# SmartThermo2_0.net
KiCad netlist of a schematic drawn in EAGLE
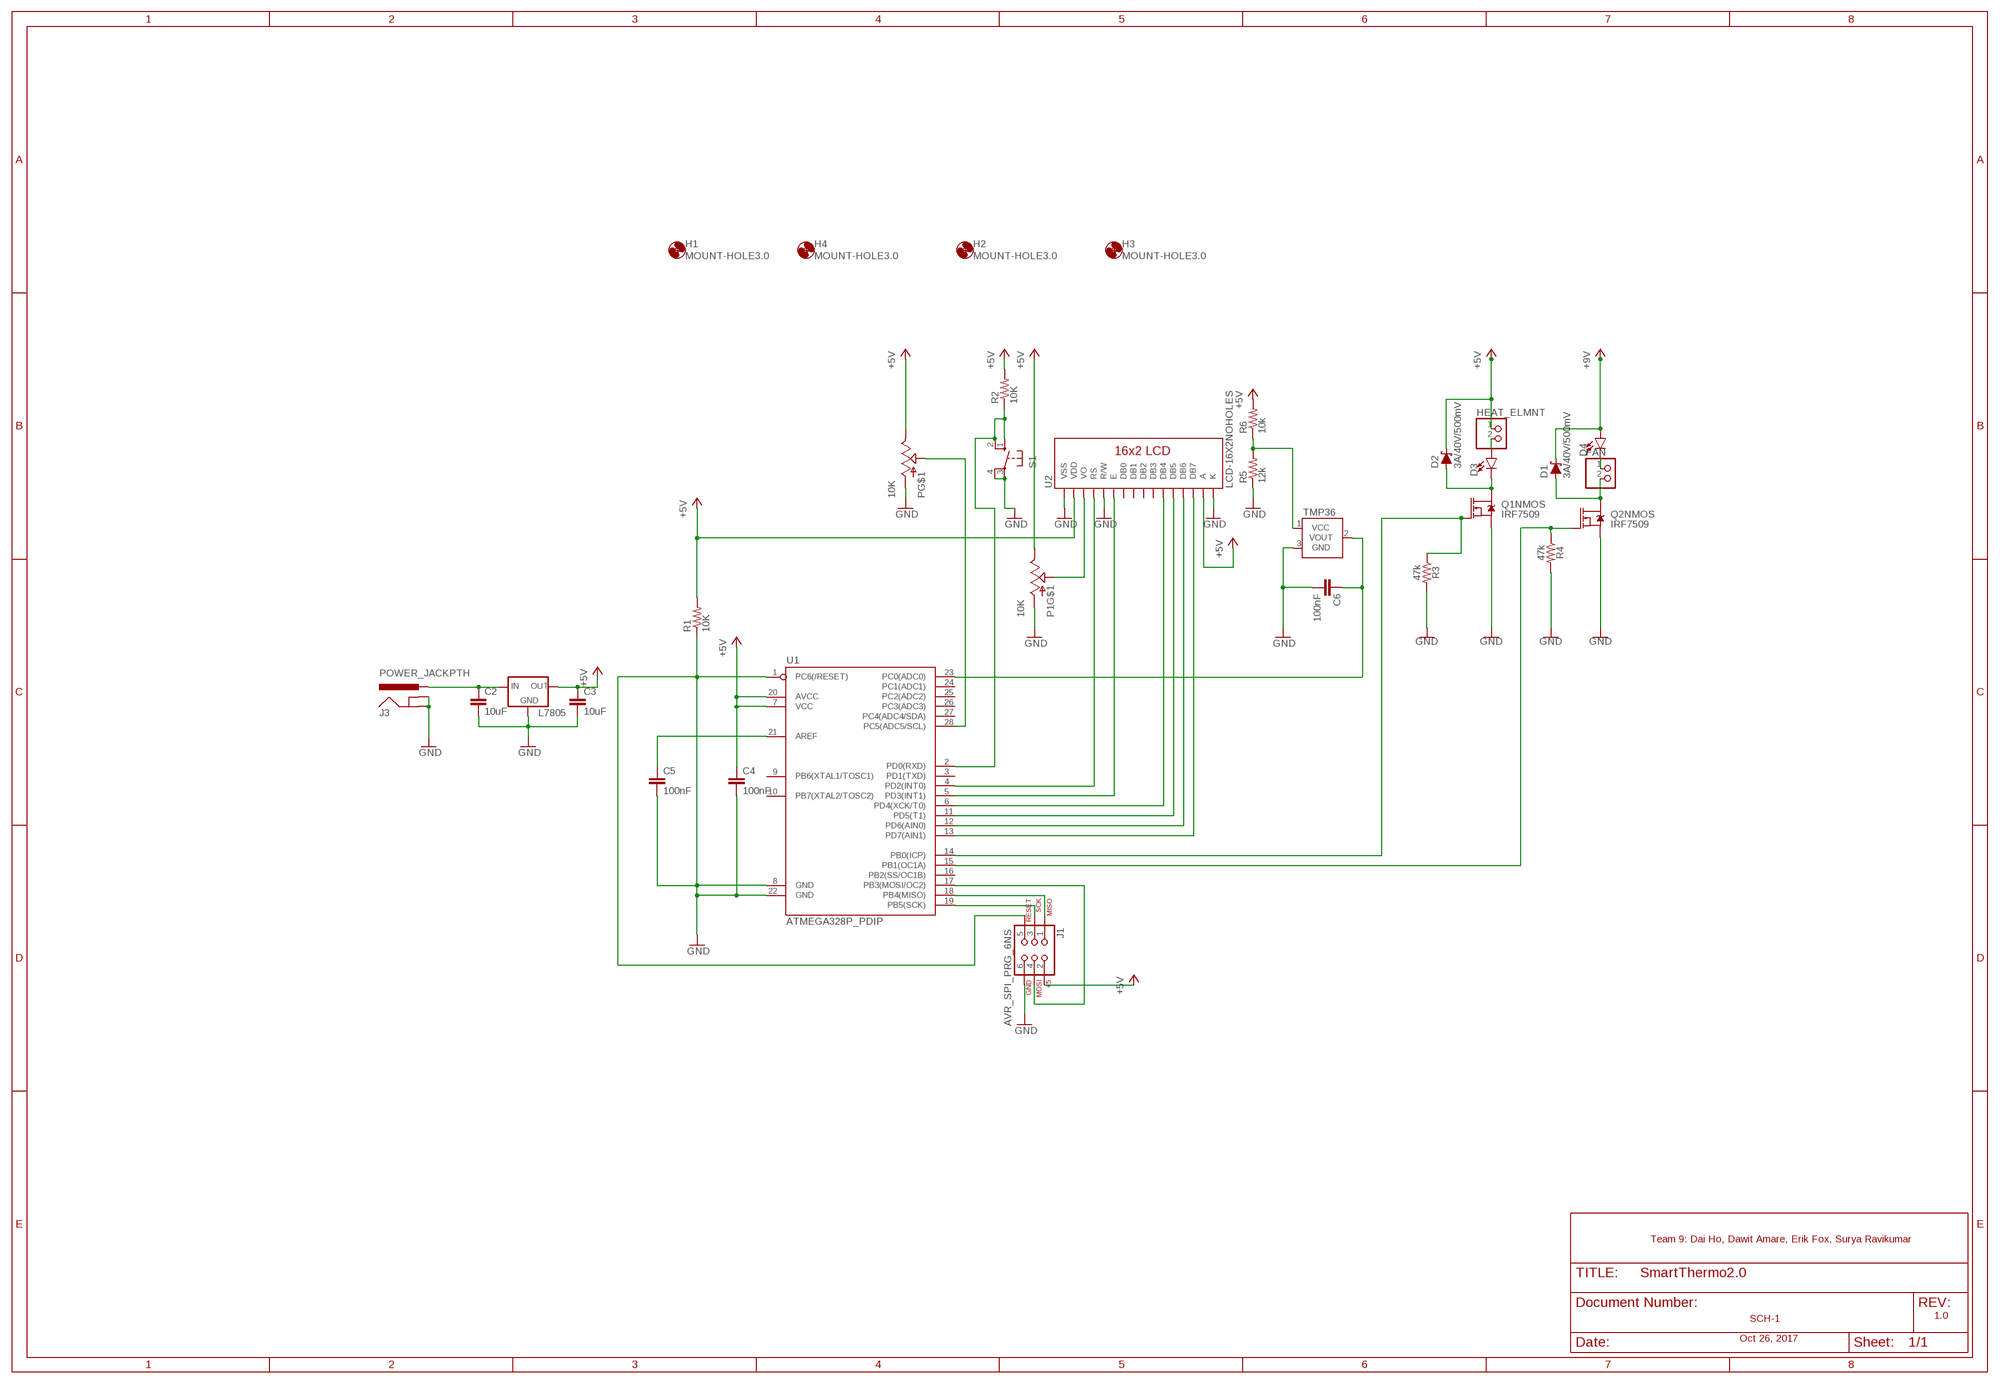
[diagram p0: schematic, sheet 1]

(export (version "E")
  (design (tool "Eeschema 10.0.6"))
  (components
    (comp (ref "C2")
      (value "10uF")
      (footprint "eagle-import:C7.5B3")
      (libsource (lib "eagle-import") (part "C7.5/3"))
    )
    (comp (ref "C3")
      (value "10uF")
      (footprint "eagle-import:C7.5B3")
      (libsource (lib "eagle-import") (part "C7.5/3"))
    )
    (comp (ref "C4")
      (value "100nF")
      (footprint "eagle-import:C2.5-2")
      (libsource (lib "eagle-import") (part "C2.5/2"))
    )
    (comp (ref "C5")
      (value "100nF")
      (footprint "eagle-import:C2.5-2")
      (libsource (lib "eagle-import") (part "C2.5/2"))
    )
    (comp (ref "C6")
      (value "100nF")
      (footprint "eagle-import:C2.5-2")
      (libsource (lib "eagle-import") (part "C2.5/2"))
    )
    (comp (ref "D1")
      (value "3A/40V/500mV")
      (footprint "eagle-import:SMA-DIODE")
      (libsource (lib "eagle-import") (part "DIODE-SCHOTTKY-B340A"))
    )
    (comp (ref "D2")
      (value "3A/40V/500mV")
      (footprint "eagle-import:SMA-DIODE")
      (libsource (lib "eagle-import") (part "DIODE-SCHOTTKY-B340A"))
    )
    (comp (ref "D3")
      (value "LED3MM")
      (footprint "eagle-import:LED_3MM")
      (libsource (lib "eagle-import") (part "LED3MM"))
    )
    (comp (ref "D4")
      (value "LED3MM")
      (footprint "eagle-import:LED_3MM")
      (libsource (lib "eagle-import") (part "LED3MM"))
    )
    (comp (ref "FAN")
      (value "PINHD-1X2/90")
      (footprint "eagle-import:1X02_90")
      (libsource (lib "eagle-import") (part "PINHD-1X2/90"))
    )
    (comp (ref "H1")
      (value "MOUNT-HOLE3.0")
      (footprint "eagle-import:3,0")
      (libsource (lib "eagle-import") (part "MOUNT-HOLE3.0"))
    )
    (comp (ref "H2")
      (value "MOUNT-HOLE3.0")
      (footprint "eagle-import:3,0")
      (libsource (lib "eagle-import") (part "MOUNT-HOLE3.0"))
    )
    (comp (ref "H3")
      (value "MOUNT-HOLE3.0")
      (footprint "eagle-import:3,0")
      (libsource (lib "eagle-import") (part "MOUNT-HOLE3.0"))
    )
    (comp (ref "H4")
      (value "MOUNT-HOLE3.0")
      (footprint "eagle-import:3,0")
      (libsource (lib "eagle-import") (part "MOUNT-HOLE3.0"))
    )
    (comp (ref "HEAT_ELMNT")
      (value "PINHD-1X2/90")
      (footprint "eagle-import:1X02_90")
      (libsource (lib "eagle-import") (part "PINHD-1X2/90"))
    )
    (comp (ref "J1")
      (value "AVR_SPI_PRG_6NS")
      (footprint "eagle-import:2X3-NS")
      (libsource (lib "eagle-import") (part "AVR_SPI_PRG_6NS"))
    )
    (comp (ref "J3")
      (value "POWER_JACKPTH")
      (footprint "eagle-import:POWER_JACK_PTH")
      (libsource (lib "eagle-import") (part "POWER_JACKPTH"))
    )
    (comp (ref "L7805")
      (value "78XXL")
      (footprint "eagle-import:78XXL")
      (libsource (lib "eagle-import") (part "78XXL"))
    )
    (comp (ref "P")
      (value "10K")
      (footprint "eagle-import:POT_PTH")
      (libsource (lib "eagle-import") (part "POT_SWITCHPOT_PTH"))
    )
    (comp (ref "P1")
      (value "10K")
      (footprint "eagle-import:POT_PTH")
      (libsource (lib "eagle-import") (part "POT_SWITCHPOT_PTH"))
    )
    (comp (ref "Q1")
      (value "IRF7509")
      (footprint "eagle-import:MSOP8")
      (libsource (lib "eagle-import") (part "IRF7509"))
    )
    (comp (ref "Q2")
      (value "IRF7509")
      (footprint "eagle-import:MSOP8")
      (libsource (lib "eagle-import") (part "IRF7509"))
    )
    (comp (ref "R1")
      (value "10K")
      (footprint "eagle-import:1206")
      (libsource (lib "eagle-import") (part "RESISTOR1206"))
    )
    (comp (ref "R2")
      (value "10K")
      (footprint "eagle-import:1206")
      (libsource (lib "eagle-import") (part "RESISTOR1206"))
    )
    (comp (ref "R3")
      (value "47k")
      (footprint "eagle-import:0603")
      (libsource (lib "eagle-import") (part "47KOHM-0603-1/10W-1%"))
    )
    (comp (ref "R4")
      (value "47k")
      (footprint "eagle-import:0603")
      (libsource (lib "eagle-import") (part "47KOHM-0603-1/10W-1%"))
    )
    (comp (ref "R5")
      (value "12k")
      (footprint "eagle-import:0204_5")
      (libsource (lib "eagle-import") (part "R-US_0204/5"))
    )
    (comp (ref "R6")
      (value "10k")
      (footprint "eagle-import:0204_5")
      (libsource (lib "eagle-import") (part "R-US_0204/5"))
    )
    (comp (ref "S1")
      (value "10-XX")
      (footprint "eagle-import:B3F-10XX")
      (fields (field (name "MPN") "B3F-1000"))
      (libsource (lib "eagle-import") (part "10-XX"))
    )
    (comp (ref "TMP36")
      (value "TMP36GT9")
      (footprint "eagle-import:TO-92")
      (libsource (lib "eagle-import") (part "TMP36GT9"))
    )
    (comp (ref "U1")
      (value "ATMEGA328P_PDIP")
      (footprint "eagle-import:DIL28-3")
      (libsource (lib "eagle-import") (part "ATMEGA328P_PDIP"))
    )
    (comp (ref "U2")
      (value "LCD-16X2NOHOLES")
      (footprint "eagle-import:LCD-16X2_NOHOLES")
      (libsource (lib "eagle-import") (part "LCD-16X2NOHOLES"))
    )
  )
  (nets
    (net (code "1") (name "+5V") (class "Default")
      (node (ref "C3") (pin "1") (pinfunction "1_1") (pintype "passive"))
      (node (ref "C4") (pin "1") (pinfunction "1_1") (pintype "passive"))
      (node (ref "D1") (pin "C") (pinfunction "C_C") (pintype "passive"))
      (node (ref "D2") (pin "C") (pinfunction "C_C") (pintype "passive"))
      (node (ref "D4") (pin "A") (pinfunction "A_A") (pintype "passive"))
      (node (ref "HEAT_ELMNT") (pin "1") (pinfunction "1_1") (pintype "passive"))
      (node (ref "J1") (pin "2") (pinfunction "2_2") (pintype "passive"))
      (node (ref "L7805") (pin "OUT") (pinfunction "OUT_OUT") (pintype "passive"))
      (node (ref "P") (pin "E@2") (pinfunction "E_E@2") (pintype "passive"))
      (node (ref "P1") (pin "E@2") (pinfunction "E_E@2") (pintype "passive"))
      (node (ref "R1") (pin "2") (pinfunction "2_2") (pintype "passive"))
      (node (ref "R2") (pin "2") (pinfunction "2_2") (pintype "passive"))
      (node (ref "R6") (pin "2") (pinfunction "2_2") (pintype "passive"))
      (node (ref "U1") (pin "20") (pinfunction "AVCC_20") (pintype "bidirectional"))
      (node (ref "U1") (pin "7") (pinfunction "VCC_7") (pintype "bidirectional"))
      (node (ref "U2") (pin "15") (pinfunction "A_15") (pintype "power_in"))
      (node (ref "U2") (pin "2") (pinfunction "VDD_2") (pintype "power_in"))
    )
    (net (code "2") (name "GND") (class "Default")
      (node (ref "C2") (pin "2") (pinfunction "2_2") (pintype "passive"))
      (node (ref "C3") (pin "2") (pinfunction "2_2") (pintype "passive"))
      (node (ref "C4") (pin "2") (pinfunction "2_2") (pintype "passive"))
      (node (ref "C5") (pin "2") (pinfunction "2_2") (pintype "passive"))
      (node (ref "C6") (pin "2") (pinfunction "2_2") (pintype "passive"))
      (node (ref "J1") (pin "5") (pinfunction "5_5") (pintype "passive"))
      (node (ref "J1") (pin "6") (pinfunction "6_6") (pintype "passive"))
      (node (ref "J3") (pin "GND") (pinfunction "GND_GND") (pintype "bidirectional"))
      (node (ref "J3") (pin "GNDBREAK") (pinfunction "GNDBREAK_GNDBREAK") (pintype "bidirectional"))
      (node (ref "L7805") (pin "GND") (pinfunction "GND_GND") (pintype "input"))
      (node (ref "P") (pin "E@1") (pinfunction "A_E@1") (pintype "passive"))
      (node (ref "P1") (pin "E@1") (pinfunction "A_E@1") (pintype "passive"))
      (node (ref "Q1") (pin "1") (pinfunction "S_1") (pintype "bidirectional"))
      (node (ref "Q2") (pin "1") (pinfunction "S_1") (pintype "bidirectional"))
      (node (ref "R1") (pin "1") (pinfunction "1_1") (pintype "passive"))
      (node (ref "R3") (pin "2") (pinfunction "2_2") (pintype "passive"))
      (node (ref "R4") (pin "2") (pinfunction "2_2") (pintype "passive"))
      (node (ref "R5") (pin "1") (pinfunction "1_1") (pintype "passive"))
      (node (ref "S1") (pin "3") (pinfunction "P_3") (pintype "passive"))
      (node (ref "S1") (pin "4") (pinfunction "P1_4") (pintype "passive"))
      (node (ref "TMP36") (pin "3") (pinfunction "GND_3") (pintype "bidirectional"))
      (node (ref "U1") (pin "1") (pinfunction "PC6(/RESET)_1") (pintype "bidirectional"))
      (node (ref "U1") (pin "22") (pinfunction "GND_22") (pintype "bidirectional"))
      (node (ref "U1") (pin "8") (pinfunction "GND_8") (pintype "bidirectional"))
      (node (ref "U2") (pin "1") (pinfunction "VSS_1") (pintype "power_in"))
      (node (ref "U2") (pin "16") (pinfunction "K_16") (pintype "power_in"))
      (node (ref "U2") (pin "5") (pinfunction "R/W_5") (pintype "input"))
    )
    (net (code "3") (name "Net-(C2-Pad1)") (class "Default")
      (node (ref "C2") (pin "1") (pinfunction "1_1") (pintype "passive"))
      (node (ref "J3") (pin "PWR") (pinfunction "PWR_PWR") (pintype "bidirectional"))
      (node (ref "L7805") (pin "IN") (pinfunction "IN_IN") (pintype "input"))
    )
    (net (code "4") (name "Net-(D1-PadA)") (class "Default")
      (node (ref "D1") (pin "A") (pinfunction "A_A") (pintype "passive"))
      (node (ref "FAN") (pin "2") (pinfunction "2_2") (pintype "passive"))
      (node (ref "Q2") (pin "7") (pinfunction "D_7") (pintype "bidirectional"))
      (node (ref "Q2") (pin "8") (pinfunction "D_8") (pintype "bidirectional"))
    )
    (net (code "5") (name "Net-(D3-C)") (class "Default")
      (node (ref "D2") (pin "A") (pinfunction "A_A") (pintype "passive"))
      (node (ref "D3") (pin "K") (pinfunction "C_K") (pintype "passive"))
      (node (ref "Q1") (pin "7") (pinfunction "D_7") (pintype "bidirectional"))
      (node (ref "Q1") (pin "8") (pinfunction "D_8") (pintype "bidirectional"))
    )
    (net (code "6") (name "Net-(D3-PadA)") (class "Default")
      (node (ref "D3") (pin "A") (pinfunction "A_A") (pintype "passive"))
      (node (ref "HEAT_ELMNT") (pin "2") (pinfunction "2_2") (pintype "passive"))
    )
    (net (code "7") (name "Net-(D4-C)") (class "Default")
      (node (ref "D4") (pin "K") (pinfunction "C_K") (pintype "passive"))
      (node (ref "FAN") (pin "1") (pinfunction "1_1") (pintype "passive"))
    )
    (net (code "8") (name "Net-(P1A-S)") (class "Default")
      (node (ref "P1") (pin "WAND") (pinfunction "S_WAND") (pintype "passive"))
      (node (ref "U2") (pin "3") (pinfunction "VO_3") (pintype "bidirectional"))
    )
    (net (code "9") (name "Net-(PA-S)") (class "Default")
      (node (ref "P") (pin "WAND") (pinfunction "S_WAND") (pintype "passive"))
      (node (ref "U1") (pin "28") (pinfunction "PC5(ADC5/SCL)_28") (pintype "bidirectional"))
    )
    (net (code "10") (name "Net-(Q1A-G)") (class "Default")
      (node (ref "Q1") (pin "2") (pinfunction "G_2") (pintype "bidirectional"))
      (node (ref "R3") (pin "1") (pinfunction "1_1") (pintype "passive"))
      (node (ref "U1") (pin "14") (pinfunction "PB0(ICP)_14") (pintype "bidirectional"))
    )
    (net (code "11") (name "Net-(Q2A-G)") (class "Default")
      (node (ref "Q2") (pin "2") (pinfunction "G_2") (pintype "bidirectional"))
      (node (ref "R4") (pin "1") (pinfunction "1_1") (pintype "passive"))
      (node (ref "U1") (pin "15") (pinfunction "PB1(OC1A)_15") (pintype "bidirectional"))
    )
    (net (code "12") (name "Net-(S1-S)") (class "Default")
      (node (ref "R2") (pin "1") (pinfunction "1_1") (pintype "passive"))
      (node (ref "S1") (pin "1") (pinfunction "S_1") (pintype "passive"))
      (node (ref "S1") (pin "2") (pinfunction "S1_2") (pintype "passive"))
      (node (ref "U1") (pin "2") (pinfunction "PD0(RXD)_2") (pintype "bidirectional"))
    )
    (net (code "13") (name "Net-(TMP36-VCC)") (class "Default")
      (node (ref "R5") (pin "2") (pinfunction "2_2") (pintype "passive"))
      (node (ref "R6") (pin "1") (pinfunction "1_1") (pintype "passive"))
      (node (ref "TMP36") (pin "1") (pinfunction "VCC_1") (pintype "bidirectional"))
    )
    (net (code "14") (name "Net-(TMP36-VOUT)") (class "Default")
      (node (ref "C6") (pin "1") (pinfunction "1_1") (pintype "passive"))
      (node (ref "TMP36") (pin "2") (pinfunction "VOUT_2") (pintype "bidirectional"))
      (node (ref "U1") (pin "23") (pinfunction "PC0(ADC0)_23") (pintype "bidirectional"))
    )
    (net (code "15") (name "Net-(U1-AREF)") (class "Default")
      (node (ref "C5") (pin "1") (pinfunction "1_1") (pintype "passive"))
      (node (ref "U1") (pin "21") (pinfunction "AREF_21") (pintype "bidirectional"))
    )
    (net (code "16") (name "Net-(U1-PB3(MOSI{slash}OC2))") (class "Default")
      (node (ref "J1") (pin "4") (pinfunction "4_4") (pintype "passive"))
      (node (ref "U1") (pin "17") (pinfunction "PB3(MOSI/OC2)_17") (pintype "bidirectional"))
    )
    (net (code "17") (name "Net-(U1-PB4(MISO))") (class "Default")
      (node (ref "J1") (pin "1") (pinfunction "1_1") (pintype "passive"))
      (node (ref "U1") (pin "18") (pinfunction "PB4(MISO)_18") (pintype "bidirectional"))
    )
    (net (code "18") (name "Net-(U1-PB5(SCK))") (class "Default")
      (node (ref "J1") (pin "3") (pinfunction "3_3") (pintype "passive"))
      (node (ref "U1") (pin "19") (pinfunction "PB5(SCK)_19") (pintype "bidirectional"))
    )
    (net (code "19") (name "Net-(U1-PD2(INT0))") (class "Default")
      (node (ref "U1") (pin "4") (pinfunction "PD2(INT0)_4") (pintype "bidirectional"))
      (node (ref "U2") (pin "4") (pinfunction "RS_4") (pintype "input"))
    )
    (net (code "20") (name "Net-(U1-PD3(INT1))") (class "Default")
      (node (ref "U1") (pin "5") (pinfunction "PD3(INT1)_5") (pintype "bidirectional"))
      (node (ref "U2") (pin "6") (pinfunction "E_6") (pintype "input"))
    )
    (net (code "21") (name "Net-(U1-PD4(XCK{slash}T0))") (class "Default")
      (node (ref "U1") (pin "6") (pinfunction "PD4(XCK/T0)_6") (pintype "bidirectional"))
      (node (ref "U2") (pin "11") (pinfunction "DB4_11") (pintype "bidirectional"))
    )
    (net (code "22") (name "Net-(U1-PD5(T1))") (class "Default")
      (node (ref "U1") (pin "11") (pinfunction "PD5(T1)_11") (pintype "bidirectional"))
      (node (ref "U2") (pin "12") (pinfunction "DB5_12") (pintype "bidirectional"))
    )
    (net (code "23") (name "Net-(U1-PD6(AIN0))") (class "Default")
      (node (ref "U1") (pin "12") (pinfunction "PD6(AIN0)_12") (pintype "bidirectional"))
      (node (ref "U2") (pin "13") (pinfunction "DB6_13") (pintype "bidirectional"))
    )
    (net (code "24") (name "Net-(U1-PD7(AIN1))") (class "Default")
      (node (ref "U1") (pin "13") (pinfunction "PD7(AIN1)_13") (pintype "bidirectional"))
      (node (ref "U2") (pin "14") (pinfunction "DB7_14") (pintype "bidirectional"))
    )
    (net (code "25") (name "unconnected-(U1-PB2(SS{slash}OC1B)-Pad16)") (class "Default")
      (node (ref "U1") (pin "16") (pinfunction "PB2(SS/OC1B)_16") (pintype "bidirectional"))
    )
    (net (code "26") (name "unconnected-(U1-PB6(XTAL1{slash}TOSC1)-Pad9)") (class "Default")
      (node (ref "U1") (pin "9") (pinfunction "PB6(XTAL1/TOSC1)_9") (pintype "bidirectional"))
    )
    (net (code "27") (name "unconnected-(U1-PB7(XTAL2{slash}TOSC2)-Pad10)") (class "Default")
      (node (ref "U1") (pin "10") (pinfunction "PB7(XTAL2/TOSC2)_10") (pintype "bidirectional"))
    )
    (net (code "28") (name "unconnected-(U1-PC1(ADC1)-Pad24)") (class "Default")
      (node (ref "U1") (pin "24") (pinfunction "PC1(ADC1)_24") (pintype "bidirectional"))
    )
    (net (code "29") (name "unconnected-(U1-PC2(ADC2)-Pad25)") (class "Default")
      (node (ref "U1") (pin "25") (pinfunction "PC2(ADC2)_25") (pintype "bidirectional"))
    )
    (net (code "30") (name "unconnected-(U1-PC3(ADC3)-Pad26)") (class "Default")
      (node (ref "U1") (pin "26") (pinfunction "PC3(ADC3)_26") (pintype "bidirectional"))
    )
    (net (code "31") (name "unconnected-(U1-PC4(ADC4{slash}SDA)-Pad27)") (class "Default")
      (node (ref "U1") (pin "27") (pinfunction "PC4(ADC4/SDA)_27") (pintype "bidirectional"))
    )
    (net (code "32") (name "unconnected-(U1-PD1(TXD)-Pad3)") (class "Default")
      (node (ref "U1") (pin "3") (pinfunction "PD1(TXD)_3") (pintype "bidirectional"))
    )
    (net (code "33") (name "unconnected-(U2-DB0-Pad7)") (class "Default")
      (node (ref "U2") (pin "7") (pinfunction "DB0_7") (pintype "bidirectional"))
    )
    (net (code "34") (name "unconnected-(U2-DB1-Pad8)") (class "Default")
      (node (ref "U2") (pin "8") (pinfunction "DB1_8") (pintype "bidirectional"))
    )
    (net (code "35") (name "unconnected-(U2-DB2-Pad9)") (class "Default")
      (node (ref "U2") (pin "9") (pinfunction "DB2_9") (pintype "bidirectional"))
    )
    (net (code "36") (name "unconnected-(U2-DB3-Pad10)") (class "Default")
      (node (ref "U2") (pin "10") (pinfunction "DB3_10") (pintype "bidirectional"))
    )
  )
)
